# encoder_counter_double.net
KiCad netlist of a schematic drawn in EAGLE
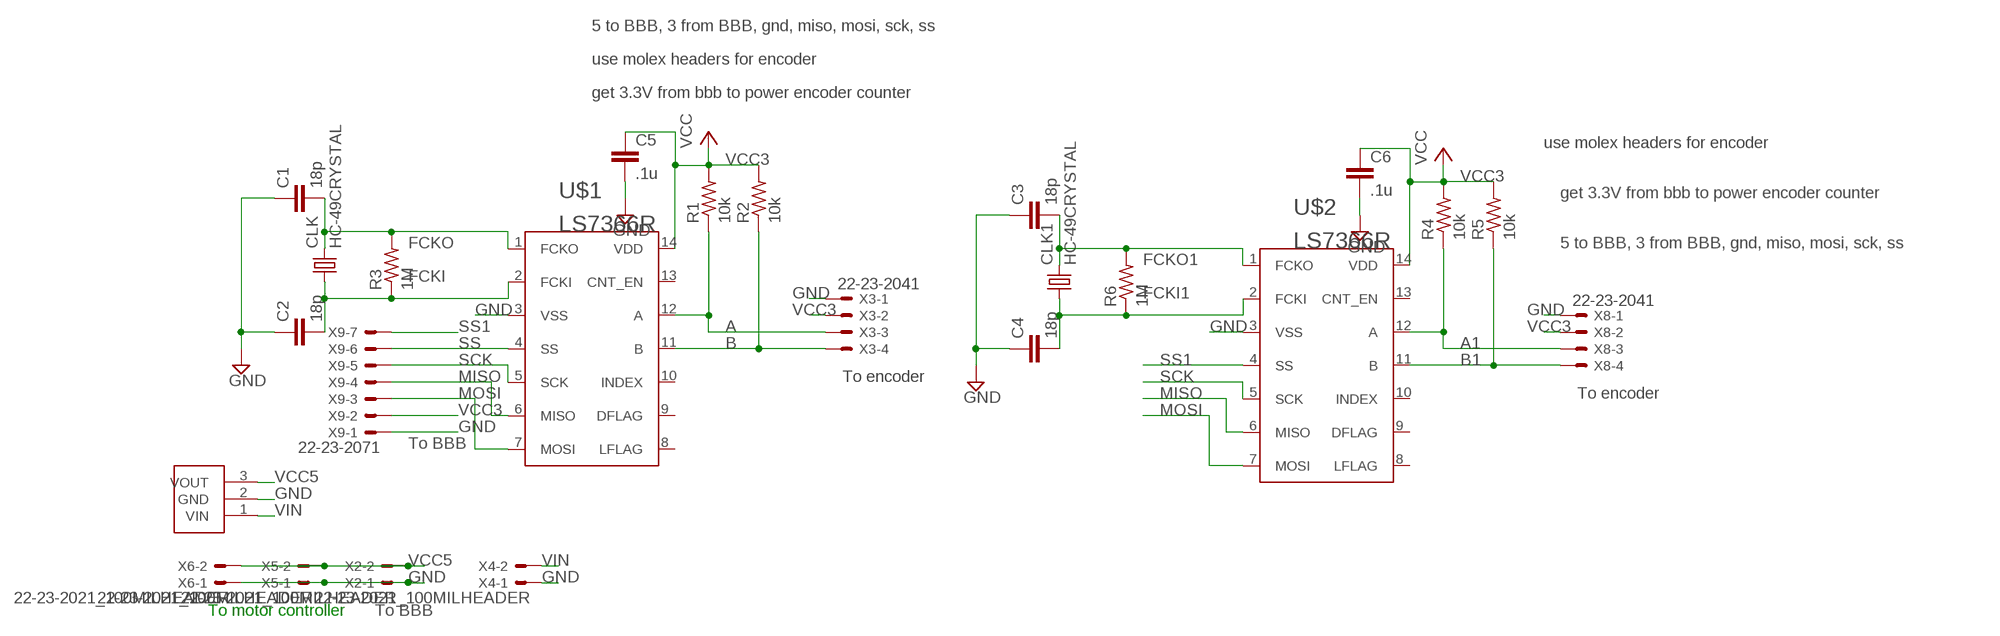
[diagram p0: schematic, sheet 1]

(export (version "E")
  (design (tool "Eeschema 10.0.6"))
  (components
    (comp (ref "C1")
      (value "18p")
      (footprint "eagle-import:C1206")
      (libsource (lib "eagle-import") (part "C-EUC1206"))
    )
    (comp (ref "C2")
      (value "18p")
      (footprint "eagle-import:C1206")
      (libsource (lib "eagle-import") (part "C-EUC1206"))
    )
    (comp (ref "C3")
      (value "18p")
      (footprint "eagle-import:C1206")
      (libsource (lib "eagle-import") (part "C-EUC1206"))
    )
    (comp (ref "C4")
      (value "18p")
      (footprint "eagle-import:C1206")
      (libsource (lib "eagle-import") (part "C-EUC1206"))
    )
    (comp (ref "C5")
      (value ".1u")
      (footprint "eagle-import:C1206")
      (libsource (lib "eagle-import") (part "C-EUC1206"))
    )
    (comp (ref "C6")
      (value ".1u")
      (footprint "eagle-import:C1206")
      (libsource (lib "eagle-import") (part "C-EUC1206"))
    )
    (comp (ref "CLK")
      (value "HC-49CRYSTAL")
      (footprint "eagle-import:HC49_S")
      (libsource (lib "eagle-import") (part "HC-49CRYSTAL"))
    )
    (comp (ref "CLK1")
      (value "HC-49CRYSTAL")
      (footprint "eagle-import:HC49_S")
      (libsource (lib "eagle-import") (part "HC-49CRYSTAL"))
    )
    (comp (ref "R1")
      (value "10k")
      (footprint "eagle-import:R1206")
      (libsource (lib "eagle-import") (part "R-US_R1206"))
    )
    (comp (ref "R2")
      (value "10k")
      (footprint "eagle-import:R1206")
      (libsource (lib "eagle-import") (part "R-US_R1206"))
    )
    (comp (ref "R3")
      (value "1M")
      (footprint "eagle-import:R1206")
      (libsource (lib "eagle-import") (part "R-US_R1206"))
    )
    (comp (ref "R4")
      (value "10k")
      (footprint "eagle-import:R1206")
      (libsource (lib "eagle-import") (part "R-US_R1206"))
    )
    (comp (ref "R5")
      (value "10k")
      (footprint "eagle-import:R1206")
      (libsource (lib "eagle-import") (part "R-US_R1206"))
    )
    (comp (ref "R6")
      (value "1M")
      (footprint "eagle-import:R1206")
      (libsource (lib "eagle-import") (part "R-US_R1206"))
    )
    (comp (ref "U$1")
      (value "LS7366R")
      (footprint "eagle-import:SO14")
      (libsource (lib "eagle-import") (part "LS7366R"))
    )
    (comp (ref "U$2")
      (value "LS7366R")
      (footprint "eagle-import:SO14")
      (libsource (lib "eagle-import") (part "LS7366R"))
    )
    (comp (ref "U$3")
      (value "OKI-78SR-X_3PIN-DCDC")
      (footprint "eagle-import:MA03-1")
      (libsource (lib "eagle-import") (part "OKI-78SR-X_3PIN-DCDC"))
    )
    (comp (ref "X2")
      (value "22-23-2021_100MILHEADER")
      (footprint "eagle-import:22-23-2021_199MILHEADER")
      (fields (field (name "MF") "MOLEX") (field (name "MPN") "22-23-2021"))
      (libsource (lib "eagle-import") (part "22-23-2021_100MILHEADER"))
    )
    (comp (ref "X3")
      (value "22-23-2041")
      (footprint "eagle-import:22-23-2041")
      (fields (field (name "MF") "MOLEX"))
      (libsource (lib "eagle-import") (part "22-23-2041"))
    )
    (comp (ref "X4")
      (value "22-23-2021_100MILHEADER")
      (footprint "eagle-import:22-23-2021_199MILHEADER")
      (fields (field (name "MF") "MOLEX") (field (name "MPN") "22-23-2021"))
      (libsource (lib "eagle-import") (part "22-23-2021_100MILHEADER"))
    )
    (comp (ref "X5")
      (value "22-23-2021_100MILHEADER")
      (footprint "eagle-import:22-23-2021_199MILHEADER")
      (fields (field (name "MF") "MOLEX") (field (name "MPN") "22-23-2021"))
      (libsource (lib "eagle-import") (part "22-23-2021_100MILHEADER"))
    )
    (comp (ref "X6")
      (value "22-23-2021_100MILHEADER")
      (footprint "eagle-import:22-23-2021_199MILHEADER")
      (fields (field (name "MF") "MOLEX") (field (name "MPN") "22-23-2021"))
      (libsource (lib "eagle-import") (part "22-23-2021_100MILHEADER"))
    )
    (comp (ref "X8")
      (value "22-23-2041")
      (footprint "eagle-import:22-23-2041")
      (fields (field (name "MF") "MOLEX"))
      (libsource (lib "eagle-import") (part "22-23-2041"))
    )
    (comp (ref "X9")
      (value "22-23-2071")
      (footprint "eagle-import:22-23-2071")
      (fields (field (name "MF") "MOLEX"))
      (libsource (lib "eagle-import") (part "22-23-2071"))
    )
  )
  (nets
    (net (code "1") (name "/A") (class "Default")
      (node (ref "R1") (pin "1") (pinfunction "1_1") (pintype "passive"))
      (node (ref "U$1") (pin "12") (pinfunction "A_12") (pintype "bidirectional"))
      (node (ref "X3") (pin "3") (pinfunction "S_3") (pintype "passive"))
    )
    (net (code "2") (name "/A1") (class "Default")
      (node (ref "R4") (pin "1") (pinfunction "1_1") (pintype "passive"))
      (node (ref "U$2") (pin "12") (pinfunction "A_12") (pintype "bidirectional"))
      (node (ref "X8") (pin "3") (pinfunction "S_3") (pintype "passive"))
    )
    (net (code "3") (name "/B") (class "Default")
      (node (ref "R2") (pin "1") (pinfunction "1_1") (pintype "passive"))
      (node (ref "U$1") (pin "11") (pinfunction "B_11") (pintype "bidirectional"))
      (node (ref "X3") (pin "4") (pinfunction "S_4") (pintype "passive"))
    )
    (net (code "4") (name "/B1") (class "Default")
      (node (ref "R5") (pin "1") (pinfunction "1_1") (pintype "passive"))
      (node (ref "U$2") (pin "11") (pinfunction "B_11") (pintype "bidirectional"))
      (node (ref "X8") (pin "4") (pinfunction "S_4") (pintype "passive"))
    )
    (net (code "5") (name "/FCKI") (class "Default")
      (node (ref "C2") (pin "2") (pinfunction "2_2") (pintype "passive"))
      (node (ref "CLK") (pin "1") (pinfunction "1_1") (pintype "passive"))
      (node (ref "R3") (pin "1") (pinfunction "1_1") (pintype "passive"))
      (node (ref "U$1") (pin "2") (pinfunction "FCKI_2") (pintype "bidirectional"))
    )
    (net (code "6") (name "/FCKI1") (class "Default")
      (node (ref "C4") (pin "2") (pinfunction "2_2") (pintype "passive"))
      (node (ref "CLK1") (pin "1") (pinfunction "1_1") (pintype "passive"))
      (node (ref "R6") (pin "1") (pinfunction "1_1") (pintype "passive"))
      (node (ref "U$2") (pin "2") (pinfunction "FCKI_2") (pintype "bidirectional"))
    )
    (net (code "7") (name "/FCKO") (class "Default")
      (node (ref "C1") (pin "2") (pinfunction "2_2") (pintype "passive"))
      (node (ref "CLK") (pin "2") (pinfunction "2_2") (pintype "passive"))
      (node (ref "R3") (pin "2") (pinfunction "2_2") (pintype "passive"))
      (node (ref "U$1") (pin "1") (pinfunction "FCKO_1") (pintype "bidirectional"))
    )
    (net (code "8") (name "/FCKO1") (class "Default")
      (node (ref "C3") (pin "2") (pinfunction "2_2") (pintype "passive"))
      (node (ref "CLK1") (pin "2") (pinfunction "2_2") (pintype "passive"))
      (node (ref "R6") (pin "2") (pinfunction "2_2") (pintype "passive"))
      (node (ref "U$2") (pin "1") (pinfunction "FCKO_1") (pintype "bidirectional"))
    )
    (net (code "9") (name "/MISO") (class "Default")
      (node (ref "U$1") (pin "6") (pinfunction "MISO_6") (pintype "bidirectional"))
      (node (ref "U$2") (pin "6") (pinfunction "MISO_6") (pintype "bidirectional"))
      (node (ref "X9") (pin "4") (pinfunction "S_4") (pintype "passive"))
    )
    (net (code "10") (name "/MOSI") (class "Default")
      (node (ref "U$1") (pin "7") (pinfunction "MOSI_7") (pintype "bidirectional"))
      (node (ref "U$2") (pin "7") (pinfunction "MOSI_7") (pintype "bidirectional"))
      (node (ref "X9") (pin "3") (pinfunction "S_3") (pintype "passive"))
    )
    (net (code "11") (name "/SCK") (class "Default")
      (node (ref "U$1") (pin "5") (pinfunction "SCK_5") (pintype "bidirectional"))
      (node (ref "U$2") (pin "5") (pinfunction "SCK_5") (pintype "bidirectional"))
      (node (ref "X9") (pin "5") (pinfunction "S_5") (pintype "passive"))
    )
    (net (code "12") (name "/SS") (class "Default")
      (node (ref "U$1") (pin "4") (pinfunction "SS_4") (pintype "bidirectional"))
      (node (ref "X9") (pin "6") (pinfunction "S_6") (pintype "passive"))
    )
    (net (code "13") (name "/SS1") (class "Default")
      (node (ref "U$2") (pin "4") (pinfunction "SS_4") (pintype "bidirectional"))
      (node (ref "X9") (pin "7") (pinfunction "S_7") (pintype "passive"))
    )
    (net (code "14") (name "/VCC5") (class "Default")
      (node (ref "U$3") (pin "3") (pinfunction "VOUT_3") (pintype "bidirectional"))
      (node (ref "X2") (pin "2") (pinfunction "S_2") (pintype "passive"))
      (node (ref "X5") (pin "2") (pinfunction "S_2") (pintype "passive"))
      (node (ref "X6") (pin "2") (pinfunction "S_2") (pintype "passive"))
    )
    (net (code "15") (name "/VIN") (class "Default")
      (node (ref "U$3") (pin "1") (pinfunction "VIN_1") (pintype "bidirectional"))
      (node (ref "X4") (pin "2") (pinfunction "S_2") (pintype "passive"))
    )
    (net (code "16") (name "GND") (class "Default")
      (node (ref "C1") (pin "1") (pinfunction "1_1") (pintype "passive"))
      (node (ref "C2") (pin "1") (pinfunction "1_1") (pintype "passive"))
      (node (ref "C3") (pin "1") (pinfunction "1_1") (pintype "passive"))
      (node (ref "C4") (pin "1") (pinfunction "1_1") (pintype "passive"))
      (node (ref "C5") (pin "2") (pinfunction "2_2") (pintype "passive"))
      (node (ref "C6") (pin "2") (pinfunction "2_2") (pintype "passive"))
      (node (ref "U$1") (pin "3") (pinfunction "VSS_3") (pintype "bidirectional"))
      (node (ref "U$2") (pin "3") (pinfunction "VSS_3") (pintype "bidirectional"))
      (node (ref "U$3") (pin "2") (pinfunction "GND_2") (pintype "bidirectional"))
      (node (ref "X2") (pin "1") (pinfunction "S_1") (pintype "passive"))
      (node (ref "X3") (pin "1") (pinfunction "S_1") (pintype "passive"))
      (node (ref "X4") (pin "1") (pinfunction "S_1") (pintype "passive"))
      (node (ref "X5") (pin "1") (pinfunction "S_1") (pintype "passive"))
      (node (ref "X6") (pin "1") (pinfunction "S_1") (pintype "passive"))
      (node (ref "X8") (pin "1") (pinfunction "S_1") (pintype "passive"))
      (node (ref "X9") (pin "1") (pinfunction "S_1") (pintype "passive"))
    )
    (net (code "17") (name "VCC") (class "Default")
      (node (ref "C5") (pin "1") (pinfunction "1_1") (pintype "passive"))
      (node (ref "C6") (pin "1") (pinfunction "1_1") (pintype "passive"))
      (node (ref "R1") (pin "2") (pinfunction "2_2") (pintype "passive"))
      (node (ref "R2") (pin "2") (pinfunction "2_2") (pintype "passive"))
      (node (ref "R4") (pin "2") (pinfunction "2_2") (pintype "passive"))
      (node (ref "R5") (pin "2") (pinfunction "2_2") (pintype "passive"))
      (node (ref "U$1") (pin "14") (pinfunction "VDD_14") (pintype "bidirectional"))
      (node (ref "U$2") (pin "14") (pinfunction "VDD_14") (pintype "bidirectional"))
      (node (ref "X3") (pin "2") (pinfunction "S_2") (pintype "passive"))
      (node (ref "X8") (pin "2") (pinfunction "S_2") (pintype "passive"))
      (node (ref "X9") (pin "2") (pinfunction "S_2") (pintype "passive"))
    )
    (net (code "18") (name "unconnected-(U$1-CNT_EN-Pad13)") (class "Default")
      (node (ref "U$1") (pin "13") (pinfunction "CNT_EN_13") (pintype "bidirectional"))
    )
    (net (code "19") (name "unconnected-(U$1-DFLAG-Pad9)") (class "Default")
      (node (ref "U$1") (pin "9") (pinfunction "DFLAG_9") (pintype "bidirectional"))
    )
    (net (code "20") (name "unconnected-(U$1-INDEX-Pad10)") (class "Default")
      (node (ref "U$1") (pin "10") (pinfunction "INDEX_10") (pintype "bidirectional"))
    )
    (net (code "21") (name "unconnected-(U$1-LFLAG-Pad8)") (class "Default")
      (node (ref "U$1") (pin "8") (pinfunction "LFLAG_8") (pintype "bidirectional"))
    )
    (net (code "22") (name "unconnected-(U$2-CNT_EN-Pad13)") (class "Default")
      (node (ref "U$2") (pin "13") (pinfunction "CNT_EN_13") (pintype "bidirectional"))
    )
    (net (code "23") (name "unconnected-(U$2-DFLAG-Pad9)") (class "Default")
      (node (ref "U$2") (pin "9") (pinfunction "DFLAG_9") (pintype "bidirectional"))
    )
    (net (code "24") (name "unconnected-(U$2-INDEX-Pad10)") (class "Default")
      (node (ref "U$2") (pin "10") (pinfunction "INDEX_10") (pintype "bidirectional"))
    )
    (net (code "25") (name "unconnected-(U$2-LFLAG-Pad8)") (class "Default")
      (node (ref "U$2") (pin "8") (pinfunction "LFLAG_8") (pintype "bidirectional"))
    )
  )
)
